# SerialLineShiftRegs.net
KiCad netlist of a schematic drawn in Altium Designer
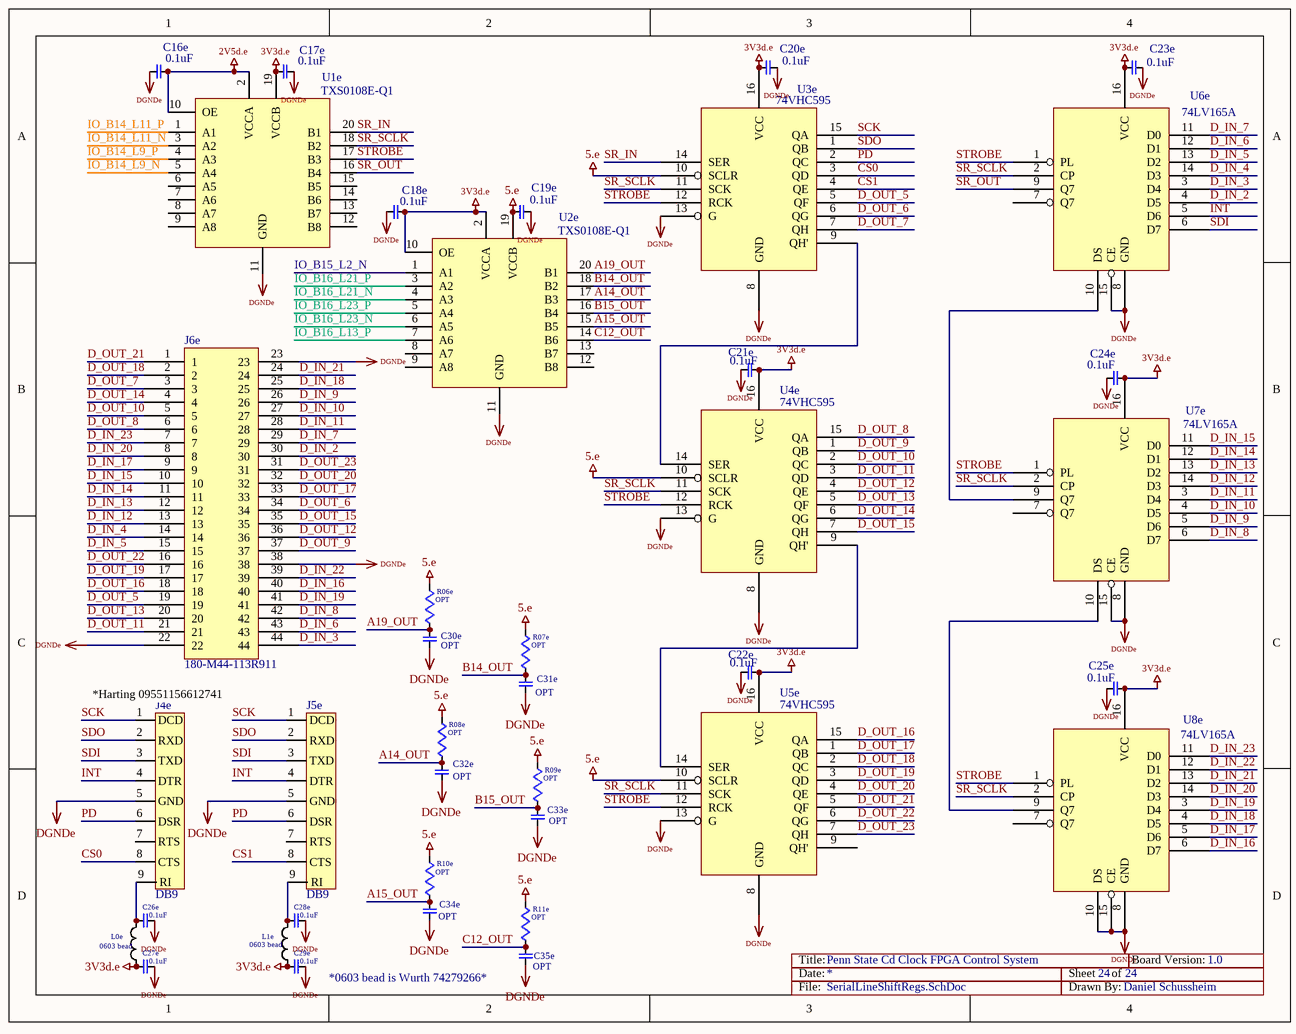
[diagram p0: SerialLineShiftRegs.SchDoc]

(export (version "E")
  (design (tool "Eeschema 10.0.6"))
  (components
    (comp (ref "C16e")
      (value "0.1uF")
      (footprint "0603")
      (libsource (lib "Mercury_AD_BaseBoard_SCHLIB") (part "CAP"))
    )
    (comp (ref "C17e")
      (value "0.1uF")
      (footprint "0603")
      (libsource (lib "Mercury_AD_BaseBoard_SCHLIB") (part "CAP"))
    )
    (comp (ref "C18e")
      (value "0.1uF")
      (footprint "0603")
      (libsource (lib "Mercury_AD_BaseBoard_SCHLIB") (part "CAP"))
    )
    (comp (ref "C19e")
      (value "0.1uF")
      (footprint "0603")
      (libsource (lib "Mercury_AD_BaseBoard_SCHLIB") (part "CAP"))
    )
    (comp (ref "C20e")
      (value "0.1uF")
      (footprint "0603")
      (libsource (lib "Mercury_AD_BaseBoard_SCHLIB") (part "CAP"))
    )
    (comp (ref "C21e")
      (value "0.1uF")
      (footprint "0603")
      (libsource (lib "Mercury_AD_BaseBoard_SCHLIB") (part "CAP"))
    )
    (comp (ref "C22e")
      (value "0.1uF")
      (footprint "0603")
      (libsource (lib "Mercury_AD_BaseBoard_SCHLIB") (part "CAP"))
    )
    (comp (ref "C23e")
      (value "0.1uF")
      (footprint "0603")
      (libsource (lib "Mercury_AD_BaseBoard_SCHLIB") (part "CAP"))
    )
    (comp (ref "C24e")
      (value "0.1uF")
      (footprint "0603")
      (libsource (lib "Mercury_AD_BaseBoard_SCHLIB") (part "CAP"))
    )
    (comp (ref "C25e")
      (value "0.1uF")
      (footprint "0603")
      (libsource (lib "Mercury_AD_BaseBoard_SCHLIB") (part "CAP"))
    )
    (comp (ref "C26e")
      (value "0.1uF")
      (footprint "0603")
      (libsource (lib "Mercury_AD_BaseBoard_SCHLIB") (part "CAP"))
    )
    (comp (ref "C27e")
      (value "0.1uF")
      (footprint "0603")
      (libsource (lib "Mercury_AD_BaseBoard_SCHLIB") (part "CAP"))
    )
    (comp (ref "C28e")
      (value "0.1uF")
      (footprint "0603")
      (libsource (lib "Mercury_AD_BaseBoard_SCHLIB") (part "CAP"))
    )
    (comp (ref "C29e")
      (value "0.1uF")
      (footprint "0603")
      (libsource (lib "Mercury_AD_BaseBoard_SCHLIB") (part "CAP"))
    )
    (comp (ref "C30e")
      (value "OPT")
      (footprint "0603")
      (libsource (lib "Mercury_AD_BaseBoard_SCHLIB") (part "CAP"))
    )
    (comp (ref "C31e")
      (value "OPT")
      (footprint "0603")
      (libsource (lib "Mercury_AD_BaseBoard_SCHLIB") (part "CAP"))
    )
    (comp (ref "C32e")
      (value "OPT")
      (footprint "0603")
      (libsource (lib "Mercury_AD_BaseBoard_SCHLIB") (part "CAP"))
    )
    (comp (ref "C33e")
      (value "OPT")
      (footprint "0603")
      (libsource (lib "Mercury_AD_BaseBoard_SCHLIB") (part "CAP"))
    )
    (comp (ref "C34e")
      (value "OPT")
      (footprint "0603")
      (libsource (lib "Mercury_AD_BaseBoard_SCHLIB") (part "CAP"))
    )
    (comp (ref "C35e")
      (value "OPT")
      (footprint "0603")
      (libsource (lib "Mercury_AD_BaseBoard_SCHLIB") (part "CAP"))
    )
    (comp (ref "J4e")
      (value "DB9")
      (footprint "9-Pin_D-Connector_SMT")
      (libsource (lib "Mercury_AD_BaseBoard_SCHLIB") (part "DB9"))
    )
    (comp (ref "J5e")
      (value "DB9")
      (footprint "9-Pin_D-Connector_SMT")
      (libsource (lib "Mercury_AD_BaseBoard_SCHLIB") (part "DB9"))
    )
    (comp (ref "J6e")
      (value "180-M44-113R911")
      (footprint "180-M44-213R911")
      (libsource (lib "Mercury_AD_BaseBoard_SCHLIB") (part "DSUB44"))
    )
    (comp (ref "L0e")
      (value "0603 bead")
      (footprint "0603")
      (libsource (lib "Mercury_AD_BaseBoard_SCHLIB") (part "INDUCTOR"))
    )
    (comp (ref "L1e")
      (value "0603 bead")
      (footprint "0603")
      (libsource (lib "Mercury_AD_BaseBoard_SCHLIB") (part "INDUCTOR"))
    )
    (comp (ref "R06e")
      (value "OPT")
      (footprint "0603")
      (libsource (lib "Mercury_AD_BaseBoard_SCHLIB") (part "RES"))
    )
    (comp (ref "R07e")
      (value "OPT")
      (footprint "0603")
      (libsource (lib "Mercury_AD_BaseBoard_SCHLIB") (part "RES"))
    )
    (comp (ref "R08e")
      (value "OPT")
      (footprint "0603")
      (libsource (lib "Mercury_AD_BaseBoard_SCHLIB") (part "RES"))
    )
    (comp (ref "R09e")
      (value "OPT")
      (footprint "0603")
      (libsource (lib "Mercury_AD_BaseBoard_SCHLIB") (part "RES"))
    )
    (comp (ref "R10e")
      (value "OPT")
      (footprint "0603")
      (libsource (lib "Mercury_AD_BaseBoard_SCHLIB") (part "RES"))
    )
    (comp (ref "R11e")
      (value "OPT")
      (footprint "0603")
      (libsource (lib "Mercury_AD_BaseBoard_SCHLIB") (part "RES"))
    )
    (comp (ref "U1e")
      (value "TXS0108E-Q1")
      (footprint "R-PDSO-G20")
      (libsource (lib "Mercury_AD_BaseBoard_SCHLIB") (part "8BitLevelShifter"))
    )
    (comp (ref "U2e")
      (value "TXS0108E-Q1")
      (footprint "R-PDSO-G20")
      (libsource (lib "Mercury_AD_BaseBoard_SCHLIB") (part "8BitLevelShifter"))
    )
    (comp (ref "U3e")
      (value "74VHC595")
      (footprint "16TSSOP")
      (libsource (lib "Mercury_AD_BaseBoard_SCHLIB") (part "74VHC595"))
    )
    (comp (ref "U4e")
      (value "74VHC595")
      (footprint "16TSSOP")
      (libsource (lib "Mercury_AD_BaseBoard_SCHLIB") (part "74VHC595"))
    )
    (comp (ref "U5e")
      (value "74VHC595")
      (footprint "16TSSOP")
      (libsource (lib "Mercury_AD_BaseBoard_SCHLIB") (part "74VHC595"))
    )
    (comp (ref "U6e")
      (value "74LV165A")
      (footprint "16TSSOP")
      (libsource (lib "Mercury_AD_BaseBoard_SCHLIB") (part "74LV165A"))
    )
    (comp (ref "U7e")
      (value "74LV165A")
      (footprint "16TSSOP")
      (libsource (lib "Mercury_AD_BaseBoard_SCHLIB") (part "74LV165A"))
    )
    (comp (ref "U8e")
      (value "74LV165A")
      (footprint "16TSSOP")
      (libsource (lib "Mercury_AD_BaseBoard_SCHLIB") (part "74LV165A"))
    )
  )
  (nets
    (net (code "1") (name "/A14_OUT") (class "Default")
      (node (ref "C32e") (pin "1") (pintype "passive"))
      (node (ref "R08e") (pin "2") (pintype "passive"))
      (node (ref "U2e") (pin "17") (pinfunction "B3_17") (pintype "passive"))
    )
    (net (code "2") (name "/A15_OUT") (class "Default")
      (node (ref "C34e") (pin "1") (pintype "passive"))
      (node (ref "R10e") (pin "2") (pintype "passive"))
      (node (ref "U2e") (pin "15") (pinfunction "B5_15") (pintype "passive"))
    )
    (net (code "3") (name "/A19_OUT") (class "Default")
      (node (ref "C30e") (pin "1") (pintype "passive"))
      (node (ref "R06e") (pin "2") (pintype "passive"))
      (node (ref "U2e") (pin "20") (pinfunction "B1_20") (pintype "passive"))
    )
    (net (code "4") (name "/B14_OUT") (class "Default")
      (node (ref "C31e") (pin "1") (pintype "passive"))
      (node (ref "R07e") (pin "2") (pintype "passive"))
      (node (ref "U2e") (pin "18") (pinfunction "B2_18") (pintype "passive"))
    )
    (net (code "5") (name "/B15_OUT") (class "Default")
      (node (ref "C33e") (pin "1") (pintype "passive"))
      (node (ref "R09e") (pin "2") (pintype "passive"))
      (node (ref "U2e") (pin "16") (pinfunction "B4_16") (pintype "passive"))
    )
    (net (code "6") (name "/C12_OUT") (class "Default")
      (node (ref "C35e") (pin "1") (pintype "passive"))
      (node (ref "R11e") (pin "2") (pintype "passive"))
      (node (ref "U2e") (pin "14") (pinfunction "B6_14") (pintype "passive"))
    )
    (net (code "7") (name "/CS0") (class "Default")
      (node (ref "J4e") (pin "8") (pinfunction "CTS_8") (pintype "passive"))
      (node (ref "U3e") (pin "3") (pinfunction "QD_3") (pintype "passive"))
    )
    (net (code "8") (name "/CS1") (class "Default")
      (node (ref "J5e") (pin "8") (pinfunction "CTS_8") (pintype "passive"))
      (node (ref "U3e") (pin "4") (pinfunction "QE_4") (pintype "passive"))
    )
    (net (code "9") (name "/D_IN_2") (class "Default")
      (node (ref "J6e") (pin "30") (pinfunction "30_30") (pintype "passive"))
      (node (ref "U6e") (pin "4") (pinfunction "D5_4") (pintype "passive"))
    )
    (net (code "10") (name "/D_IN_3") (class "Default")
      (node (ref "J6e") (pin "44") (pinfunction "44_44") (pintype "passive"))
      (node (ref "U6e") (pin "3") (pinfunction "D4_3") (pintype "passive"))
    )
    (net (code "11") (name "/D_IN_4") (class "Default")
      (node (ref "J6e") (pin "14") (pinfunction "14_14") (pintype "passive"))
      (node (ref "U6e") (pin "14") (pinfunction "D3_14") (pintype "passive"))
    )
    (net (code "12") (name "/D_IN_5") (class "Default")
      (node (ref "J6e") (pin "15") (pinfunction "15_15") (pintype "passive"))
      (node (ref "U6e") (pin "13") (pinfunction "D2_13") (pintype "passive"))
    )
    (net (code "13") (name "/D_IN_6") (class "Default")
      (node (ref "J6e") (pin "43") (pinfunction "43_43") (pintype "passive"))
      (node (ref "U6e") (pin "12") (pinfunction "D1_12") (pintype "passive"))
    )
    (net (code "14") (name "/D_IN_7") (class "Default")
      (node (ref "J6e") (pin "29") (pinfunction "29_29") (pintype "passive"))
      (node (ref "U6e") (pin "11") (pinfunction "D0_11") (pintype "passive"))
    )
    (net (code "15") (name "/D_IN_8") (class "Default")
      (node (ref "J6e") (pin "42") (pinfunction "42_42") (pintype "passive"))
      (node (ref "U7e") (pin "6") (pinfunction "D7_6") (pintype "passive"))
    )
    (net (code "16") (name "/D_IN_9") (class "Default")
      (node (ref "J6e") (pin "26") (pinfunction "26_26") (pintype "passive"))
      (node (ref "U7e") (pin "5") (pinfunction "D6_5") (pintype "passive"))
    )
    (net (code "17") (name "/D_IN_10") (class "Default")
      (node (ref "J6e") (pin "27") (pinfunction "27_27") (pintype "passive"))
      (node (ref "U7e") (pin "4") (pinfunction "D5_4") (pintype "passive"))
    )
    (net (code "18") (name "/D_IN_11") (class "Default")
      (node (ref "J6e") (pin "28") (pinfunction "28_28") (pintype "passive"))
      (node (ref "U7e") (pin "3") (pinfunction "D4_3") (pintype "passive"))
    )
    (net (code "19") (name "/D_IN_12") (class "Default")
      (node (ref "J6e") (pin "13") (pinfunction "13_13") (pintype "passive"))
      (node (ref "U7e") (pin "14") (pinfunction "D3_14") (pintype "passive"))
    )
    (net (code "20") (name "/D_IN_13") (class "Default")
      (node (ref "J6e") (pin "12") (pinfunction "12_12") (pintype "passive"))
      (node (ref "U7e") (pin "13") (pinfunction "D2_13") (pintype "passive"))
    )
    (net (code "21") (name "/D_IN_14") (class "Default")
      (node (ref "J6e") (pin "11") (pinfunction "11_11") (pintype "passive"))
      (node (ref "U7e") (pin "12") (pinfunction "D1_12") (pintype "passive"))
    )
    (net (code "22") (name "/D_IN_15") (class "Default")
      (node (ref "J6e") (pin "10") (pinfunction "10_10") (pintype "passive"))
      (node (ref "U7e") (pin "11") (pinfunction "D0_11") (pintype "passive"))
    )
    (net (code "23") (name "/D_IN_16") (class "Default")
      (node (ref "J6e") (pin "40") (pinfunction "40_40") (pintype "passive"))
      (node (ref "U8e") (pin "6") (pinfunction "D7_6") (pintype "passive"))
    )
    (net (code "24") (name "/D_IN_17") (class "Default")
      (node (ref "J6e") (pin "9") (pinfunction "9_9") (pintype "passive"))
      (node (ref "U8e") (pin "5") (pinfunction "D6_5") (pintype "passive"))
    )
    (net (code "25") (name "/D_IN_18") (class "Default")
      (node (ref "J6e") (pin "25") (pinfunction "25_25") (pintype "passive"))
      (node (ref "U8e") (pin "4") (pinfunction "D5_4") (pintype "passive"))
    )
    (net (code "26") (name "/D_IN_19") (class "Default")
      (node (ref "J6e") (pin "41") (pinfunction "41_41") (pintype "passive"))
      (node (ref "U8e") (pin "3") (pinfunction "D4_3") (pintype "passive"))
    )
    (net (code "27") (name "/D_IN_20") (class "Default")
      (node (ref "J6e") (pin "8") (pinfunction "8_8") (pintype "passive"))
      (node (ref "U8e") (pin "14") (pinfunction "D3_14") (pintype "passive"))
    )
    (net (code "28") (name "/D_IN_21") (class "Default")
      (node (ref "J6e") (pin "24") (pinfunction "24_24") (pintype "passive"))
      (node (ref "U8e") (pin "13") (pinfunction "D2_13") (pintype "passive"))
    )
    (net (code "29") (name "/D_IN_22") (class "Default")
      (node (ref "J6e") (pin "39") (pinfunction "39_39") (pintype "passive"))
      (node (ref "U8e") (pin "12") (pinfunction "D1_12") (pintype "passive"))
    )
    (net (code "30") (name "/D_IN_23") (class "Default")
      (node (ref "J6e") (pin "7") (pinfunction "7_7") (pintype "passive"))
      (node (ref "U8e") (pin "11") (pinfunction "D0_11") (pintype "passive"))
    )
    (net (code "31") (name "/D_OUT_5") (class "Default")
      (node (ref "J6e") (pin "19") (pinfunction "19_19") (pintype "passive"))
      (node (ref "U3e") (pin "5") (pinfunction "QF_5") (pintype "passive"))
    )
    (net (code "32") (name "/D_OUT_6") (class "Default")
      (node (ref "J6e") (pin "34") (pinfunction "34_34") (pintype "passive"))
      (node (ref "U3e") (pin "6") (pinfunction "QG_6") (pintype "passive"))
    )
    (net (code "33") (name "/D_OUT_7") (class "Default")
      (node (ref "J6e") (pin "3") (pinfunction "3_3") (pintype "passive"))
      (node (ref "U3e") (pin "7") (pinfunction "QH_7") (pintype "passive"))
    )
    (net (code "34") (name "/D_OUT_8") (class "Default")
      (node (ref "J6e") (pin "6") (pinfunction "6_6") (pintype "passive"))
      (node (ref "U4e") (pin "15") (pinfunction "QA_15") (pintype "passive"))
    )
    (net (code "35") (name "/D_OUT_9") (class "Default")
      (node (ref "J6e") (pin "37") (pinfunction "37_37") (pintype "passive"))
      (node (ref "U4e") (pin "1") (pinfunction "QB_1") (pintype "passive"))
    )
    (net (code "36") (name "/D_OUT_10") (class "Default")
      (node (ref "J6e") (pin "5") (pinfunction "5_5") (pintype "passive"))
      (node (ref "U4e") (pin "2") (pinfunction "QC_2") (pintype "passive"))
    )
    (net (code "37") (name "/D_OUT_11") (class "Default")
      (node (ref "J6e") (pin "21") (pinfunction "21_21") (pintype "passive"))
      (node (ref "U4e") (pin "3") (pinfunction "QD_3") (pintype "passive"))
    )
    (net (code "38") (name "/D_OUT_12") (class "Default")
      (node (ref "J6e") (pin "36") (pinfunction "36_36") (pintype "passive"))
      (node (ref "U4e") (pin "4") (pinfunction "QE_4") (pintype "passive"))
    )
    (net (code "39") (name "/D_OUT_13") (class "Default")
      (node (ref "J6e") (pin "20") (pinfunction "20_20") (pintype "passive"))
      (node (ref "U4e") (pin "5") (pinfunction "QF_5") (pintype "passive"))
    )
    (net (code "40") (name "/D_OUT_14") (class "Default")
      (node (ref "J6e") (pin "4") (pinfunction "4_4") (pintype "passive"))
      (node (ref "U4e") (pin "6") (pinfunction "QG_6") (pintype "passive"))
    )
    (net (code "41") (name "/D_OUT_15") (class "Default")
      (node (ref "J6e") (pin "35") (pinfunction "35_35") (pintype "passive"))
      (node (ref "U4e") (pin "7") (pinfunction "QH_7") (pintype "passive"))
    )
    (net (code "42") (name "/D_OUT_16") (class "Default")
      (node (ref "J6e") (pin "18") (pinfunction "18_18") (pintype "passive"))
      (node (ref "U5e") (pin "15") (pinfunction "QA_15") (pintype "passive"))
    )
    (net (code "43") (name "/D_OUT_17") (class "Default")
      (node (ref "J6e") (pin "33") (pinfunction "33_33") (pintype "passive"))
      (node (ref "U5e") (pin "1") (pinfunction "QB_1") (pintype "passive"))
    )
    (net (code "44") (name "/D_OUT_18") (class "Default")
      (node (ref "J6e") (pin "2") (pinfunction "2_2") (pintype "passive"))
      (node (ref "U5e") (pin "2") (pinfunction "QC_2") (pintype "passive"))
    )
    (net (code "45") (name "/D_OUT_19") (class "Default")
      (node (ref "J6e") (pin "17") (pinfunction "17_17") (pintype "passive"))
      (node (ref "U5e") (pin "3") (pinfunction "QD_3") (pintype "passive"))
    )
    (net (code "46") (name "/D_OUT_20") (class "Default")
      (node (ref "J6e") (pin "32") (pinfunction "32_32") (pintype "passive"))
      (node (ref "U5e") (pin "4") (pinfunction "QE_4") (pintype "passive"))
    )
    (net (code "47") (name "/D_OUT_21") (class "Default")
      (node (ref "J6e") (pin "1") (pinfunction "1_1") (pintype "passive"))
      (node (ref "U5e") (pin "5") (pinfunction "QF_5") (pintype "passive"))
    )
    (net (code "48") (name "/D_OUT_22") (class "Default")
      (node (ref "J6e") (pin "16") (pinfunction "16_16") (pintype "passive"))
      (node (ref "U5e") (pin "6") (pinfunction "QG_6") (pintype "passive"))
    )
    (net (code "49") (name "/D_OUT_23") (class "Default")
      (node (ref "J6e") (pin "31") (pinfunction "31_31") (pintype "passive"))
      (node (ref "U5e") (pin "7") (pinfunction "QH_7") (pintype "passive"))
    )
    (net (code "50") (name "/INT") (class "Default")
      (node (ref "J4e") (pin "4") (pinfunction "DTR_4") (pintype "passive"))
      (node (ref "J5e") (pin "4") (pinfunction "DTR_4") (pintype "passive"))
      (node (ref "U6e") (pin "5") (pinfunction "D6_5") (pintype "passive"))
    )
    (net (code "51") (name "/IO_B14_L9_N") (class "Default")
      (node (ref "U1e") (pin "5") (pinfunction "A4_5") (pintype "passive"))
    )
    (net (code "52") (name "/IO_B14_L9_P") (class "Default")
      (node (ref "U1e") (pin "4") (pinfunction "A3_4") (pintype "passive"))
    )
    (net (code "53") (name "/IO_B14_L11_N") (class "Default")
      (node (ref "U1e") (pin "3") (pinfunction "A2_3") (pintype "passive"))
    )
    (net (code "54") (name "/IO_B14_L11_P") (class "Default")
      (node (ref "U1e") (pin "1") (pinfunction "A1_1") (pintype "passive"))
    )
    (net (code "55") (name "/IO_B15_L2_N") (class "Default")
      (node (ref "U2e") (pin "1") (pinfunction "A1_1") (pintype "passive"))
    )
    (net (code "56") (name "/IO_B16_L13_P") (class "Default")
      (node (ref "U2e") (pin "7") (pinfunction "A6_7") (pintype "passive"))
    )
    (net (code "57") (name "/IO_B16_L21_N") (class "Default")
      (node (ref "U2e") (pin "4") (pinfunction "A3_4") (pintype "passive"))
    )
    (net (code "58") (name "/IO_B16_L21_P") (class "Default")
      (node (ref "U2e") (pin "3") (pinfunction "A2_3") (pintype "passive"))
    )
    (net (code "59") (name "/IO_B16_L23_N") (class "Default")
      (node (ref "U2e") (pin "6") (pinfunction "A5_6") (pintype "passive"))
    )
    (net (code "60") (name "/IO_B16_L23_P") (class "Default")
      (node (ref "U2e") (pin "5") (pinfunction "A4_5") (pintype "passive"))
    )
    (net (code "61") (name "/PD") (class "Default")
      (node (ref "J4e") (pin "6") (pinfunction "DSR_6") (pintype "passive"))
      (node (ref "J5e") (pin "6") (pinfunction "DSR_6") (pintype "passive"))
      (node (ref "U3e") (pin "2") (pinfunction "QC_2") (pintype "passive"))
    )
    (net (code "62") (name "/SCK") (class "Default")
      (node (ref "J4e") (pin "1") (pinfunction "DCD_1") (pintype "passive"))
      (node (ref "J5e") (pin "1") (pinfunction "DCD_1") (pintype "passive"))
      (node (ref "U3e") (pin "15") (pinfunction "QA_15") (pintype "passive"))
    )
    (net (code "63") (name "/SDI") (class "Default")
      (node (ref "J4e") (pin "3") (pinfunction "TXD_3") (pintype "passive"))
      (node (ref "J5e") (pin "3") (pinfunction "TXD_3") (pintype "passive"))
      (node (ref "U6e") (pin "6") (pinfunction "D7_6") (pintype "passive"))
    )
    (net (code "64") (name "/SDO") (class "Default")
      (node (ref "J4e") (pin "2") (pinfunction "RXD_2") (pintype "passive"))
      (node (ref "J5e") (pin "2") (pinfunction "RXD_2") (pintype "passive"))
      (node (ref "U3e") (pin "1") (pinfunction "QB_1") (pintype "passive"))
    )
    (net (code "65") (name "/SR_IN") (class "Default")
      (node (ref "U1e") (pin "20") (pinfunction "B1_20") (pintype "passive"))
      (node (ref "U3e") (pin "14") (pinfunction "SER_14") (pintype "passive"))
    )
    (net (code "66") (name "/SR_OUT") (class "Default")
      (node (ref "U1e") (pin "16") (pinfunction "B4_16") (pintype "passive"))
      (node (ref "U6e") (pin "9") (pinfunction "Q7_9") (pintype "passive"))
    )
    (net (code "67") (name "/SR_SCLK") (class "Default")
      (node (ref "U1e") (pin "18") (pinfunction "B2_18") (pintype "passive"))
      (node (ref "U3e") (pin "11") (pinfunction "SCK_11") (pintype "passive"))
      (node (ref "U4e") (pin "11") (pinfunction "SCK_11") (pintype "passive"))
      (node (ref "U5e") (pin "11") (pinfunction "SCK_11") (pintype "passive"))
      (node (ref "U6e") (pin "2") (pinfunction "CP_2") (pintype "passive"))
      (node (ref "U7e") (pin "2") (pinfunction "CP_2") (pintype "passive"))
      (node (ref "U8e") (pin "2") (pinfunction "CP_2") (pintype "passive"))
    )
    (net (code "68") (name "/STROBE") (class "Default")
      (node (ref "U1e") (pin "17") (pinfunction "B3_17") (pintype "passive"))
      (node (ref "U3e") (pin "12") (pinfunction "RCK_12") (pintype "passive"))
      (node (ref "U4e") (pin "12") (pinfunction "RCK_12") (pintype "passive"))
      (node (ref "U5e") (pin "12") (pinfunction "RCK_12") (pintype "passive"))
      (node (ref "U6e") (pin "1") (pinfunction "PL_1") (pintype "passive"))
      (node (ref "U7e") (pin "1") (pinfunction "PL_1") (pintype "passive"))
      (node (ref "U8e") (pin "1") (pinfunction "PL_1") (pintype "passive"))
    )
    (net (code "69") (name "2V5d.e") (class "Default")
      (node (ref "C16e") (pin "1") (pintype "passive"))
      (node (ref "U1e") (pin "10") (pinfunction "OE_10") (pintype "passive"))
      (node (ref "U1e") (pin "2") (pinfunction "VCCA_2") (pintype "passive"))
    )
    (net (code "70") (name "3V3d.e") (class "Default")
      (node (ref "C17e") (pin "2") (pintype "passive"))
      (node (ref "C18e") (pin "1") (pintype "passive"))
      (node (ref "C20e") (pin "2") (pintype "passive"))
      (node (ref "C21e") (pin "1") (pintype "passive"))
      (node (ref "C22e") (pin "1") (pintype "passive"))
      (node (ref "C23e") (pin "2") (pintype "passive"))
      (node (ref "C24e") (pin "1") (pintype "passive"))
      (node (ref "C25e") (pin "1") (pintype "passive"))
      (node (ref "C27e") (pin "2") (pintype "passive"))
      (node (ref "C29e") (pin "2") (pintype "passive"))
      (node (ref "L0e") (pin "1") (pinfunction "1_1") (pintype "passive"))
      (node (ref "L1e") (pin "1") (pinfunction "1_1") (pintype "passive"))
      (node (ref "U1e") (pin "19") (pinfunction "VCCB_19") (pintype "passive"))
      (node (ref "U2e") (pin "10") (pinfunction "OE_10") (pintype "passive"))
      (node (ref "U2e") (pin "2") (pinfunction "VCCA_2") (pintype "passive"))
      (node (ref "U3e") (pin "16") (pinfunction "VCC_16") (pintype "passive"))
      (node (ref "U4e") (pin "16") (pinfunction "VCC_16") (pintype "passive"))
      (node (ref "U5e") (pin "16") (pinfunction "VCC_16") (pintype "passive"))
      (node (ref "U6e") (pin "16") (pinfunction "VCC_16") (pintype "passive"))
      (node (ref "U7e") (pin "16") (pinfunction "VCC_16") (pintype "passive"))
      (node (ref "U8e") (pin "16") (pinfunction "VCC_16") (pintype "passive"))
    )
    (net (code "71") (name "5.e") (class "Default")
      (node (ref "C19e") (pin "2") (pintype "passive"))
      (node (ref "R06e") (pin "1") (pintype "passive"))
      (node (ref "R07e") (pin "1") (pintype "passive"))
      (node (ref "R08e") (pin "1") (pintype "passive"))
      (node (ref "R09e") (pin "1") (pintype "passive"))
      (node (ref "R10e") (pin "1") (pintype "passive"))
      (node (ref "R11e") (pin "1") (pintype "passive"))
      (node (ref "U2e") (pin "19") (pinfunction "VCCB_19") (pintype "passive"))
      (node (ref "U3e") (pin "10") (pinfunction "SCLR_10") (pintype "passive"))
      (node (ref "U4e") (pin "10") (pinfunction "SCLR_10") (pintype "passive"))
      (node (ref "U5e") (pin "10") (pinfunction "SCLR_10") (pintype "passive"))
    )
    (net (code "72") (name "DGNDe") (class "Default")
      (node (ref "C16e") (pin "2") (pintype "passive"))
      (node (ref "C17e") (pin "1") (pintype "passive"))
      (node (ref "C18e") (pin "2") (pintype "passive"))
      (node (ref "C19e") (pin "1") (pintype "passive"))
      (node (ref "C20e") (pin "1") (pintype "passive"))
      (node (ref "C21e") (pin "2") (pintype "passive"))
      (node (ref "C22e") (pin "2") (pintype "passive"))
      (node (ref "C23e") (pin "1") (pintype "passive"))
      (node (ref "C24e") (pin "2") (pintype "passive"))
      (node (ref "C25e") (pin "2") (pintype "passive"))
      (node (ref "C26e") (pin "1") (pintype "passive"))
      (node (ref "C27e") (pin "1") (pintype "passive"))
      (node (ref "C28e") (pin "1") (pintype "passive"))
      (node (ref "C29e") (pin "1") (pintype "passive"))
      (node (ref "C30e") (pin "2") (pintype "passive"))
      (node (ref "C31e") (pin "2") (pintype "passive"))
      (node (ref "C32e") (pin "2") (pintype "passive"))
      (node (ref "C33e") (pin "2") (pintype "passive"))
      (node (ref "C34e") (pin "2") (pintype "passive"))
      (node (ref "C35e") (pin "2") (pintype "passive"))
      (node (ref "J4e") (pin "5") (pinfunction "GND_5") (pintype "passive"))
      (node (ref "J5e") (pin "5") (pinfunction "GND_5") (pintype "passive"))
      (node (ref "J6e") (pin "22") (pinfunction "22_22") (pintype "passive"))
      (node (ref "J6e") (pin "23") (pinfunction "23_23") (pintype "passive"))
      (node (ref "J6e") (pin "38") (pinfunction "38_38") (pintype "passive"))
      (node (ref "U1e") (pin "11") (pinfunction "GND_11") (pintype "passive"))
      (node (ref "U2e") (pin "11") (pinfunction "GND_11") (pintype "passive"))
      (node (ref "U3e") (pin "13") (pinfunction "G_13") (pintype "passive"))
      (node (ref "U3e") (pin "8") (pinfunction "GND_8") (pintype "passive"))
      (node (ref "U4e") (pin "13") (pinfunction "G_13") (pintype "passive"))
      (node (ref "U4e") (pin "8") (pinfunction "GND_8") (pintype "passive"))
      (node (ref "U5e") (pin "13") (pinfunction "G_13") (pintype "passive"))
      (node (ref "U5e") (pin "8") (pinfunction "GND_8") (pintype "passive"))
      (node (ref "U6e") (pin "15") (pinfunction "CE_15") (pintype "passive"))
      (node (ref "U6e") (pin "8") (pinfunction "GND_8") (pintype "passive"))
      (node (ref "U7e") (pin "15") (pinfunction "CE_15") (pintype "passive"))
      (node (ref "U7e") (pin "8") (pinfunction "GND_8") (pintype "passive"))
      (node (ref "U8e") (pin "10") (pinfunction "DS_10") (pintype "passive"))
      (node (ref "U8e") (pin "15") (pinfunction "CE_15") (pintype "passive"))
      (node (ref "U8e") (pin "8") (pinfunction "GND_8") (pintype "passive"))
    )
    (net (code "73") (name "Net-(J4e-RI)") (class "Default")
      (node (ref "C26e") (pin "2") (pintype "passive"))
      (node (ref "J4e") (pin "9") (pinfunction "RI_9") (pintype "passive"))
      (node (ref "L0e") (pin "2") (pinfunction "2_2") (pintype "passive"))
    )
    (net (code "74") (name "Net-(J5e-RI)") (class "Default")
      (node (ref "C28e") (pin "2") (pintype "passive"))
      (node (ref "J5e") (pin "9") (pinfunction "RI_9") (pintype "passive"))
      (node (ref "L1e") (pin "2") (pinfunction "2_2") (pintype "passive"))
    )
    (net (code "75") (name "Net-(U3e-QH')") (class "Default")
      (node (ref "U3e") (pin "9") (pinfunction "QH'_9") (pintype "passive"))
      (node (ref "U4e") (pin "14") (pinfunction "SER_14") (pintype "passive"))
    )
    (net (code "76") (name "Net-(U4e-QH')") (class "Default")
      (node (ref "U4e") (pin "9") (pinfunction "QH'_9") (pintype "passive"))
      (node (ref "U5e") (pin "14") (pinfunction "SER_14") (pintype "passive"))
    )
    (net (code "77") (name "Net-(U6e-DS)") (class "Default")
      (node (ref "U6e") (pin "10") (pinfunction "DS_10") (pintype "passive"))
      (node (ref "U7e") (pin "9") (pinfunction "Q7_9") (pintype "passive"))
    )
    (net (code "78") (name "Net-(U7e-DS)") (class "Default")
      (node (ref "U7e") (pin "10") (pinfunction "DS_10") (pintype "passive"))
      (node (ref "U8e") (pin "9") (pinfunction "Q7_9") (pintype "passive"))
    )
    (net (code "79") (name "unconnected-(J4e-RTS-Pad7)") (class "Default")
      (node (ref "J4e") (pin "7") (pinfunction "RTS_7") (pintype "passive"))
    )
    (net (code "80") (name "unconnected-(J5e-RTS-Pad7)") (class "Default")
      (node (ref "J5e") (pin "7") (pinfunction "RTS_7") (pintype "passive"))
    )
    (net (code "81") (name "unconnected-(U1e-A5-Pad6)") (class "Default")
      (node (ref "U1e") (pin "6") (pinfunction "A5_6") (pintype "passive"))
    )
    (net (code "82") (name "unconnected-(U1e-A6-Pad7)") (class "Default")
      (node (ref "U1e") (pin "7") (pinfunction "A6_7") (pintype "passive"))
    )
    (net (code "83") (name "unconnected-(U1e-A7-Pad8)") (class "Default")
      (node (ref "U1e") (pin "8") (pinfunction "A7_8") (pintype "passive"))
    )
    (net (code "84") (name "unconnected-(U1e-A8-Pad9)") (class "Default")
      (node (ref "U1e") (pin "9") (pinfunction "A8_9") (pintype "passive"))
    )
    (net (code "85") (name "unconnected-(U1e-B5-Pad15)") (class "Default")
      (node (ref "U1e") (pin "15") (pinfunction "B5_15") (pintype "passive"))
    )
    (net (code "86") (name "unconnected-(U1e-B6-Pad14)") (class "Default")
      (node (ref "U1e") (pin "14") (pinfunction "B6_14") (pintype "passive"))
    )
    (net (code "87") (name "unconnected-(U1e-B7-Pad13)") (class "Default")
      (node (ref "U1e") (pin "13") (pinfunction "B7_13") (pintype "passive"))
    )
    (net (code "88") (name "unconnected-(U1e-B8-Pad12)") (class "Default")
      (node (ref "U1e") (pin "12") (pinfunction "B8_12") (pintype "passive"))
    )
    (net (code "89") (name "unconnected-(U2e-A7-Pad8)") (class "Default")
      (node (ref "U2e") (pin "8") (pinfunction "A7_8") (pintype "passive"))
    )
    (net (code "90") (name "unconnected-(U2e-A8-Pad9)") (class "Default")
      (node (ref "U2e") (pin "9") (pinfunction "A8_9") (pintype "passive"))
    )
    (net (code "91") (name "unconnected-(U2e-B7-Pad13)") (class "Default")
      (node (ref "U2e") (pin "13") (pinfunction "B7_13") (pintype "passive"))
    )
    (net (code "92") (name "unconnected-(U2e-B8-Pad12)") (class "Default")
      (node (ref "U2e") (pin "12") (pinfunction "B8_12") (pintype "passive"))
    )
    (net (code "93") (name "unconnected-(U5e-QH'-Pad9)") (class "Default")
      (node (ref "U5e") (pin "9") (pinfunction "QH'_9") (pintype "passive"))
    )
    (net (code "94") (name "unconnected-(U6e-Q7-Pad7)") (class "Default")
      (node (ref "U6e") (pin "7") (pinfunction "Q7_7") (pintype "passive"))
    )
    (net (code "95") (name "unconnected-(U7e-Q7-Pad7)") (class "Default")
      (node (ref "U7e") (pin "7") (pinfunction "Q7_7") (pintype "passive"))
    )
    (net (code "96") (name "unconnected-(U8e-Q7-Pad7)") (class "Default")
      (node (ref "U8e") (pin "7") (pinfunction "Q7_7") (pintype "passive"))
    )
  )
)
